# 9volt_rail.net
KiCad netlist of a schematic drawn in EAGLE
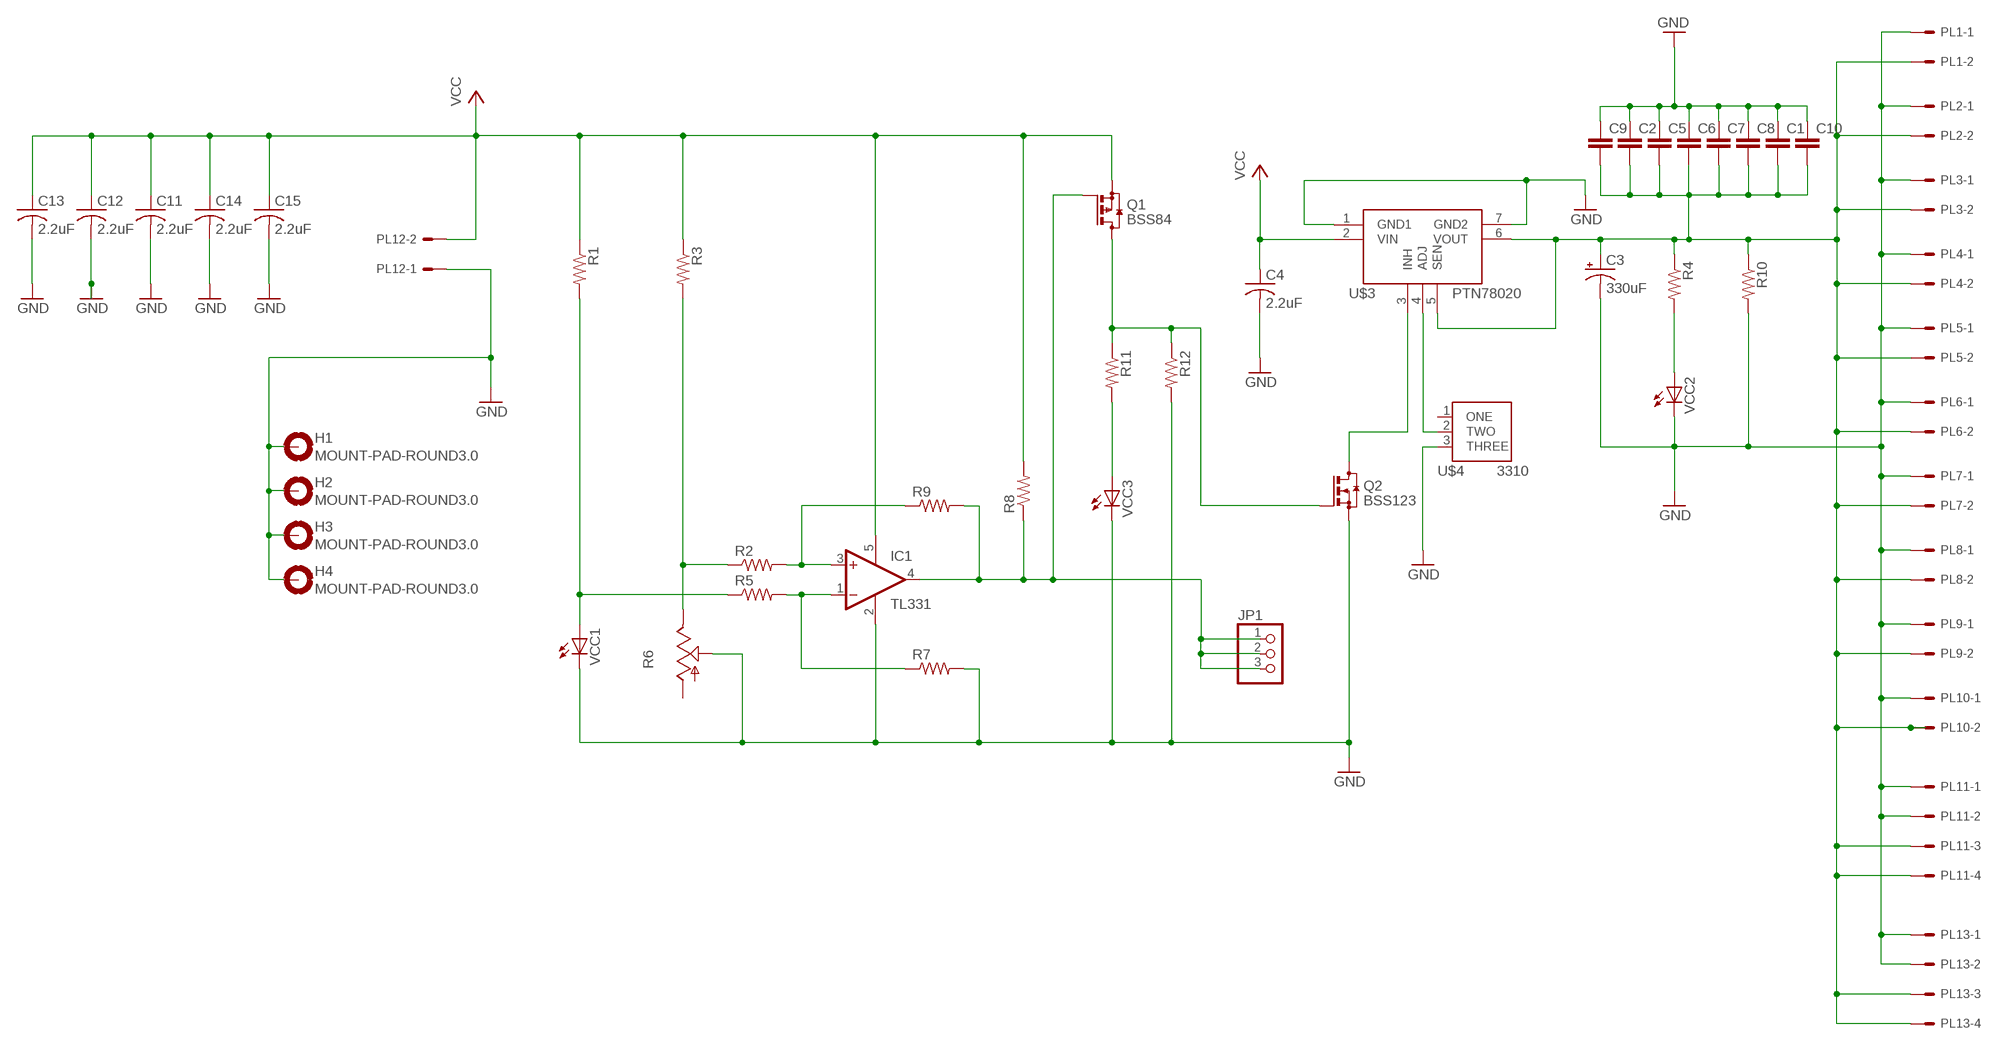
[diagram p0: schematic, sheet 1]

(export (version "E")
  (design (tool "Eeschema 10.0.6"))
  (components
    (comp (ref "C1")
      (value "C-EUC0805")
      (footprint "eagle-import:C0805")
      (libsource (lib "eagle-import") (part "C-EUC0805"))
    )
    (comp (ref "C2")
      (value "C-EUC0805")
      (footprint "eagle-import:C0805")
      (libsource (lib "eagle-import") (part "C-EUC0805"))
    )
    (comp (ref "C3")
      (value "330uF")
      (footprint "eagle-import:E5-10,5")
      (libsource (lib "eagle-import") (part "CPOL-USE5-10.5"))
    )
    (comp (ref "C4")
      (value "2.2uF")
      (footprint "eagle-import:C0805")
      (libsource (lib "eagle-import") (part "C-USC0805"))
    )
    (comp (ref "C5")
      (value "C-EUC0805")
      (footprint "eagle-import:C0805")
      (libsource (lib "eagle-import") (part "C-EUC0805"))
    )
    (comp (ref "C6")
      (value "C-EUC0805")
      (footprint "eagle-import:C0805")
      (libsource (lib "eagle-import") (part "C-EUC0805"))
    )
    (comp (ref "C7")
      (value "C-EUC0805")
      (footprint "eagle-import:C0805")
      (libsource (lib "eagle-import") (part "C-EUC0805"))
    )
    (comp (ref "C8")
      (value "C-EUC0805")
      (footprint "eagle-import:C0805")
      (libsource (lib "eagle-import") (part "C-EUC0805"))
    )
    (comp (ref "C9")
      (value "C-EUC0805")
      (footprint "eagle-import:C0805")
      (libsource (lib "eagle-import") (part "C-EUC0805"))
    )
    (comp (ref "C10")
      (value "C-EUC0805")
      (footprint "eagle-import:C0805")
      (libsource (lib "eagle-import") (part "C-EUC0805"))
    )
    (comp (ref "C11")
      (value "2.2uF")
      (footprint "eagle-import:C0805")
      (libsource (lib "eagle-import") (part "C-USC0805"))
    )
    (comp (ref "C12")
      (value "2.2uF")
      (footprint "eagle-import:C0805")
      (libsource (lib "eagle-import") (part "C-USC0805"))
    )
    (comp (ref "C13")
      (value "2.2uF")
      (footprint "eagle-import:C0805")
      (libsource (lib "eagle-import") (part "C-USC0805"))
    )
    (comp (ref "C14")
      (value "2.2uF")
      (footprint "eagle-import:C0805")
      (libsource (lib "eagle-import") (part "C-USC0805"))
    )
    (comp (ref "C15")
      (value "2.2uF")
      (footprint "eagle-import:C0805")
      (libsource (lib "eagle-import") (part "C-USC0805"))
    )
    (comp (ref "H1")
      (value "MOUNT-PAD-ROUND3.0")
      (footprint "eagle-import:3,0-PAD")
      (libsource (lib "eagle-import") (part "MOUNT-PAD-ROUND3.0"))
    )
    (comp (ref "H2")
      (value "MOUNT-PAD-ROUND3.0")
      (footprint "eagle-import:3,0-PAD")
      (libsource (lib "eagle-import") (part "MOUNT-PAD-ROUND3.0"))
    )
    (comp (ref "H3")
      (value "MOUNT-PAD-ROUND3.0")
      (footprint "eagle-import:3,0-PAD")
      (libsource (lib "eagle-import") (part "MOUNT-PAD-ROUND3.0"))
    )
    (comp (ref "H4")
      (value "MOUNT-PAD-ROUND3.0")
      (footprint "eagle-import:3,0-PAD")
      (libsource (lib "eagle-import") (part "MOUNT-PAD-ROUND3.0"))
    )
    (comp (ref "IC1")
      (value "TL331")
      (footprint "eagle-import:DBV-R-PDSO-G5")
      (libsource (lib "eagle-import") (part "TL331"))
    )
    (comp (ref "JP1")
      (value "PINHD-1X3")
      (footprint "eagle-import:1X03")
      (libsource (lib "eagle-import") (part "PINHD-1X3"))
    )
    (comp (ref "PL1")
      (value "555X-2H")
      (footprint "eagle-import:5569-2")
      (libsource (lib "eagle-import") (part "555X-2H"))
    )
    (comp (ref "PL2")
      (value "555X-2H")
      (footprint "eagle-import:5569-2")
      (libsource (lib "eagle-import") (part "555X-2H"))
    )
    (comp (ref "PL3")
      (value "555X-2H")
      (footprint "eagle-import:5569-2")
      (libsource (lib "eagle-import") (part "555X-2H"))
    )
    (comp (ref "PL4")
      (value "555X-2H")
      (footprint "eagle-import:5569-2")
      (libsource (lib "eagle-import") (part "555X-2H"))
    )
    (comp (ref "PL5")
      (value "555X-2H")
      (footprint "eagle-import:5569-2")
      (libsource (lib "eagle-import") (part "555X-2H"))
    )
    (comp (ref "PL6")
      (value "555X-2H")
      (footprint "eagle-import:5569-2")
      (libsource (lib "eagle-import") (part "555X-2H"))
    )
    (comp (ref "PL7")
      (value "555X-2H")
      (footprint "eagle-import:5569-2")
      (libsource (lib "eagle-import") (part "555X-2H"))
    )
    (comp (ref "PL8")
      (value "555X-2H")
      (footprint "eagle-import:5569-2")
      (libsource (lib "eagle-import") (part "555X-2H"))
    )
    (comp (ref "PL9")
      (value "555X-2H")
      (footprint "eagle-import:5569-2")
      (libsource (lib "eagle-import") (part "555X-2H"))
    )
    (comp (ref "PL10")
      (value "555X-2H")
      (footprint "eagle-import:5569-2")
      (libsource (lib "eagle-import") (part "555X-2H"))
    )
    (comp (ref "PL11")
      (value "555X-4H")
      (footprint "eagle-import:5569-4")
      (libsource (lib "eagle-import") (part "555X-4H"))
    )
    (comp (ref "PL12")
      (value "555X-2H")
      (footprint "eagle-import:5569-2")
      (libsource (lib "eagle-import") (part "555X-2H"))
    )
    (comp (ref "PL13")
      (value "555X-4H")
      (footprint "eagle-import:5569-4")
      (libsource (lib "eagle-import") (part "555X-4H"))
    )
    (comp (ref "Q1")
      (value "BSS84")
      (footprint "eagle-import:SOT23")
      (libsource (lib "eagle-import") (part "BSS84"))
    )
    (comp (ref "Q2")
      (value "BSS123")
      (footprint "eagle-import:SOT23")
      (libsource (lib "eagle-import") (part "BSS123"))
    )
    (comp (ref "R1")
      (value "R-US_M0805")
      (footprint "eagle-import:M0805")
      (libsource (lib "eagle-import") (part "R-US_M0805"))
    )
    (comp (ref "R2")
      (value "R-US_M0805")
      (footprint "eagle-import:M0805")
      (libsource (lib "eagle-import") (part "R-US_M0805"))
    )
    (comp (ref "R3")
      (value "R-US_M0805")
      (footprint "eagle-import:M0805")
      (libsource (lib "eagle-import") (part "R-US_M0805"))
    )
    (comp (ref "R4")
      (value "R-US_M0805")
      (footprint "eagle-import:M0805")
      (libsource (lib "eagle-import") (part "R-US_M0805"))
    )
    (comp (ref "R5")
      (value "R-US_M0805")
      (footprint "eagle-import:M0805")
      (libsource (lib "eagle-import") (part "R-US_M0805"))
    )
    (comp (ref "R6")
      (value "TRIM_US-RS3")
      (footprint "eagle-import:RS3")
      (libsource (lib "eagle-import") (part "TRIM_US-RS3"))
    )
    (comp (ref "R7")
      (value "R-US_M0805")
      (footprint "eagle-import:M0805")
      (libsource (lib "eagle-import") (part "R-US_M0805"))
    )
    (comp (ref "R8")
      (value "R-US_M0805")
      (footprint "eagle-import:M0805")
      (libsource (lib "eagle-import") (part "R-US_M0805"))
    )
    (comp (ref "R9")
      (value "R-US_M0805")
      (footprint "eagle-import:M0805")
      (libsource (lib "eagle-import") (part "R-US_M0805"))
    )
    (comp (ref "R10")
      (value "R-US_M0805")
      (footprint "eagle-import:M0805")
      (libsource (lib "eagle-import") (part "R-US_M0805"))
    )
    (comp (ref "R11")
      (value "R-US_M0805")
      (footprint "eagle-import:M0805")
      (libsource (lib "eagle-import") (part "R-US_M0805"))
    )
    (comp (ref "R12")
      (value "R-US_M0805")
      (footprint "eagle-import:M0805")
      (libsource (lib "eagle-import") (part "R-US_M0805"))
    )
    (comp (ref "U$3")
      (value "PTH78020-SMD")
      (footprint "eagle-import:PTN78020-SND")
      (libsource (lib "eagle-import") (part "PTH78020-SMD"))
    )
    (comp (ref "U$4")
      (value "3310-001")
      (footprint "eagle-import:3310-001-TH")
      (libsource (lib "eagle-import") (part "3310-001"))
    )
    (comp (ref "VCC1")
      (value "LED5MM")
      (footprint "eagle-import:LED5MM")
      (libsource (lib "eagle-import") (part "LED5MM"))
    )
    (comp (ref "VCC2")
      (value "LED5MM")
      (footprint "eagle-import:LED5MM")
      (libsource (lib "eagle-import") (part "LED5MM"))
    )
    (comp (ref "VCC3")
      (value "LED5MM")
      (footprint "eagle-import:LED5MM")
      (libsource (lib "eagle-import") (part "LED5MM"))
    )
  )
  (nets
    (net (code "1") (name "GND") (class "Default")
      (node (ref "C1") (pin "1") (pinfunction "1_1") (pintype "passive"))
      (node (ref "C10") (pin "1") (pinfunction "1_1") (pintype "passive"))
      (node (ref "C11") (pin "2") (pinfunction "2_2") (pintype "passive"))
      (node (ref "C12") (pin "2") (pinfunction "2_2") (pintype "passive"))
      (node (ref "C13") (pin "2") (pinfunction "2_2") (pintype "passive"))
      (node (ref "C14") (pin "2") (pinfunction "2_2") (pintype "passive"))
      (node (ref "C15") (pin "2") (pinfunction "2_2") (pintype "passive"))
      (node (ref "C2") (pin "1") (pinfunction "1_1") (pintype "passive"))
      (node (ref "C3") (pin "-") (pinfunction "-_-") (pintype "passive"))
      (node (ref "C4") (pin "2") (pinfunction "2_2") (pintype "passive"))
      (node (ref "C5") (pin "1") (pinfunction "1_1") (pintype "passive"))
      (node (ref "C6") (pin "1") (pinfunction "1_1") (pintype "passive"))
      (node (ref "C7") (pin "1") (pinfunction "1_1") (pintype "passive"))
      (node (ref "C8") (pin "1") (pinfunction "1_1") (pintype "passive"))
      (node (ref "C9") (pin "1") (pinfunction "1_1") (pintype "passive"))
      (node (ref "H1") (pin "B3,0") (pinfunction "MOUNT_B3,0") (pintype "passive"))
      (node (ref "H2") (pin "B3,0") (pinfunction "MOUNT_B3,0") (pintype "passive"))
      (node (ref "H3") (pin "B3,0") (pinfunction "MOUNT_B3,0") (pintype "passive"))
      (node (ref "H4") (pin "B3,0") (pinfunction "MOUNT_B3,0") (pintype "passive"))
      (node (ref "IC1") (pin "2") (pinfunction "GND_2") (pintype "power_in"))
      (node (ref "PL1") (pin "1") (pinfunction "S_1") (pintype "passive"))
      (node (ref "PL10") (pin "1") (pinfunction "S_1") (pintype "passive"))
      (node (ref "PL11") (pin "1") (pinfunction "S_1") (pintype "passive"))
      (node (ref "PL11") (pin "2") (pinfunction "S_2") (pintype "passive"))
      (node (ref "PL12") (pin "1") (pinfunction "S_1") (pintype "passive"))
      (node (ref "PL13") (pin "1") (pinfunction "S_1") (pintype "passive"))
      (node (ref "PL13") (pin "2") (pinfunction "S_2") (pintype "passive"))
      (node (ref "PL2") (pin "1") (pinfunction "S_1") (pintype "passive"))
      (node (ref "PL3") (pin "1") (pinfunction "S_1") (pintype "passive"))
      (node (ref "PL4") (pin "1") (pinfunction "S_1") (pintype "passive"))
      (node (ref "PL5") (pin "1") (pinfunction "S_1") (pintype "passive"))
      (node (ref "PL6") (pin "1") (pinfunction "S_1") (pintype "passive"))
      (node (ref "PL7") (pin "1") (pinfunction "S_1") (pintype "passive"))
      (node (ref "PL8") (pin "1") (pinfunction "S_1") (pintype "passive"))
      (node (ref "PL9") (pin "1") (pinfunction "S_1") (pintype "passive"))
      (node (ref "Q2") (pin "2") (pinfunction "S_2") (pintype "passive"))
      (node (ref "R10") (pin "2") (pinfunction "2_2") (pintype "passive"))
      (node (ref "R12") (pin "2") (pinfunction "2_2") (pintype "passive"))
      (node (ref "R6") (pin "S") (pinfunction "S_S") (pintype "passive"))
      (node (ref "R7") (pin "2") (pinfunction "2_2") (pintype "passive"))
      (node (ref "U$3") (pin "1") (pinfunction "GND1_1") (pintype "bidirectional"))
      (node (ref "U$3") (pin "7") (pinfunction "GND2_7") (pintype "bidirectional"))
      (node (ref "U$4") (pin "3") (pinfunction "THREE_3") (pintype "bidirectional"))
      (node (ref "VCC1") (pin "K") (pinfunction "C_K") (pintype "passive"))
      (node (ref "VCC2") (pin "K") (pinfunction "C_K") (pintype "passive"))
      (node (ref "VCC3") (pin "K") (pinfunction "C_K") (pintype "passive"))
    )
    (net (code "2") (name "Net-(IC1-+IN)") (class "Default")
      (node (ref "IC1") (pin "3") (pinfunction "+IN_3") (pintype "input"))
      (node (ref "R2") (pin "2") (pinfunction "2_2") (pintype "passive"))
      (node (ref "R9") (pin "1") (pinfunction "1_1") (pintype "passive"))
    )
    (net (code "3") (name "Net-(IC1--IN)") (class "Default")
      (node (ref "IC1") (pin "1") (pinfunction "-IN_1") (pintype "input"))
      (node (ref "R5") (pin "2") (pinfunction "2_2") (pintype "passive"))
      (node (ref "R7") (pin "1") (pinfunction "1_1") (pintype "passive"))
    )
    (net (code "4") (name "Net-(IC1-OUT)") (class "Default")
      (node (ref "IC1") (pin "4") (pinfunction "OUT_4") (pintype "output"))
      (node (ref "JP1") (pin "1") (pinfunction "1_1") (pintype "passive"))
      (node (ref "JP1") (pin "2") (pinfunction "2_2") (pintype "passive"))
      (node (ref "JP1") (pin "3") (pinfunction "3_3") (pintype "passive"))
      (node (ref "Q1") (pin "1") (pinfunction "G_1") (pintype "passive"))
      (node (ref "R8") (pin "1") (pinfunction "1_1") (pintype "passive"))
      (node (ref "R9") (pin "2") (pinfunction "2_2") (pintype "passive"))
    )
    (net (code "5") (name "Net-(PL10B-S)") (class "Default")
      (node (ref "C1") (pin "2") (pinfunction "2_2") (pintype "passive"))
      (node (ref "C10") (pin "2") (pinfunction "2_2") (pintype "passive"))
      (node (ref "C2") (pin "2") (pinfunction "2_2") (pintype "passive"))
      (node (ref "C3") (pin "+") (pinfunction "+_+") (pintype "passive"))
      (node (ref "C5") (pin "2") (pinfunction "2_2") (pintype "passive"))
      (node (ref "C6") (pin "2") (pinfunction "2_2") (pintype "passive"))
      (node (ref "C7") (pin "2") (pinfunction "2_2") (pintype "passive"))
      (node (ref "C8") (pin "2") (pinfunction "2_2") (pintype "passive"))
      (node (ref "C9") (pin "2") (pinfunction "2_2") (pintype "passive"))
      (node (ref "PL1") (pin "2") (pinfunction "S_2") (pintype "passive"))
      (node (ref "PL10") (pin "2") (pinfunction "S_2") (pintype "passive"))
      (node (ref "PL11") (pin "3") (pinfunction "S_3") (pintype "passive"))
      (node (ref "PL11") (pin "4") (pinfunction "S_4") (pintype "passive"))
      (node (ref "PL13") (pin "3") (pinfunction "S_3") (pintype "passive"))
      (node (ref "PL13") (pin "4") (pinfunction "S_4") (pintype "passive"))
      (node (ref "PL2") (pin "2") (pinfunction "S_2") (pintype "passive"))
      (node (ref "PL3") (pin "2") (pinfunction "S_2") (pintype "passive"))
      (node (ref "PL4") (pin "2") (pinfunction "S_2") (pintype "passive"))
      (node (ref "PL5") (pin "2") (pinfunction "S_2") (pintype "passive"))
      (node (ref "PL6") (pin "2") (pinfunction "S_2") (pintype "passive"))
      (node (ref "PL7") (pin "2") (pinfunction "S_2") (pintype "passive"))
      (node (ref "PL8") (pin "2") (pinfunction "S_2") (pintype "passive"))
      (node (ref "PL9") (pin "2") (pinfunction "S_2") (pintype "passive"))
      (node (ref "R10") (pin "1") (pinfunction "1_1") (pintype "passive"))
      (node (ref "R4") (pin "1") (pinfunction "1_1") (pintype "passive"))
      (node (ref "U$3") (pin "5") (pinfunction "SEN_5") (pintype "bidirectional"))
      (node (ref "U$3") (pin "6") (pinfunction "VOUT_6") (pintype "bidirectional"))
    )
    (net (code "6") (name "Net-(Q1-D)") (class "Default")
      (node (ref "Q1") (pin "3") (pinfunction "D_3") (pintype "passive"))
      (node (ref "Q2") (pin "1") (pinfunction "G_1") (pintype "passive"))
      (node (ref "R11") (pin "1") (pinfunction "1_1") (pintype "passive"))
      (node (ref "R12") (pin "1") (pinfunction "1_1") (pintype "passive"))
    )
    (net (code "7") (name "Net-(Q2-D)") (class "Default")
      (node (ref "Q2") (pin "3") (pinfunction "D_3") (pintype "passive"))
      (node (ref "U$3") (pin "3") (pinfunction "INH_3") (pintype "bidirectional"))
    )
    (net (code "8") (name "Net-(R1-Pad2)") (class "Default")
      (node (ref "R1") (pin "2") (pinfunction "2_2") (pintype "passive"))
      (node (ref "R5") (pin "1") (pinfunction "1_1") (pintype "passive"))
      (node (ref "VCC1") (pin "A") (pinfunction "A_A") (pintype "passive"))
    )
    (net (code "9") (name "Net-(R2-Pad1)") (class "Default")
      (node (ref "R2") (pin "1") (pinfunction "1_1") (pintype "passive"))
      (node (ref "R3") (pin "2") (pinfunction "2_2") (pintype "passive"))
      (node (ref "R6") (pin "E") (pinfunction "E_E") (pintype "passive"))
    )
    (net (code "10") (name "Net-(R4-Pad2)") (class "Default")
      (node (ref "R4") (pin "2") (pinfunction "2_2") (pintype "passive"))
      (node (ref "VCC2") (pin "A") (pinfunction "A_A") (pintype "passive"))
    )
    (net (code "11") (name "Net-(R11-Pad2)") (class "Default")
      (node (ref "R11") (pin "2") (pinfunction "2_2") (pintype "passive"))
      (node (ref "VCC3") (pin "A") (pinfunction "A_A") (pintype "passive"))
    )
    (net (code "12") (name "Net-(U$3-ADJ)") (class "Default")
      (node (ref "U$3") (pin "4") (pinfunction "ADJ_4") (pintype "bidirectional"))
      (node (ref "U$4") (pin "2") (pinfunction "TWO_2") (pintype "bidirectional"))
    )
    (net (code "13") (name "VCC") (class "Default")
      (node (ref "C11") (pin "1") (pinfunction "1_1") (pintype "passive"))
      (node (ref "C12") (pin "1") (pinfunction "1_1") (pintype "passive"))
      (node (ref "C13") (pin "1") (pinfunction "1_1") (pintype "passive"))
      (node (ref "C14") (pin "1") (pinfunction "1_1") (pintype "passive"))
      (node (ref "C15") (pin "1") (pinfunction "1_1") (pintype "passive"))
      (node (ref "C4") (pin "1") (pinfunction "1_1") (pintype "passive"))
      (node (ref "IC1") (pin "5") (pinfunction "V+_5") (pintype "power_in"))
      (node (ref "PL12") (pin "2") (pinfunction "S_2") (pintype "passive"))
      (node (ref "Q1") (pin "2") (pinfunction "S_2") (pintype "passive"))
      (node (ref "R1") (pin "1") (pinfunction "1_1") (pintype "passive"))
      (node (ref "R3") (pin "1") (pinfunction "1_1") (pintype "passive"))
      (node (ref "R8") (pin "2") (pinfunction "2_2") (pintype "passive"))
      (node (ref "U$3") (pin "2") (pinfunction "VIN_2") (pintype "bidirectional"))
    )
    (net (code "14") (name "unconnected-(R6-PadA)") (class "Default")
      (node (ref "R6") (pin "A") (pinfunction "A_A") (pintype "passive"))
    )
    (net (code "15") (name "unconnected-(U$4-ONE-Pad1)") (class "Default")
      (node (ref "U$4") (pin "1") (pinfunction "ONE_1") (pintype "bidirectional"))
    )
  )
)
